# Ai_Breakout_OLED-0_962.net
KiCad netlist of a schematic drawn in EAGLE
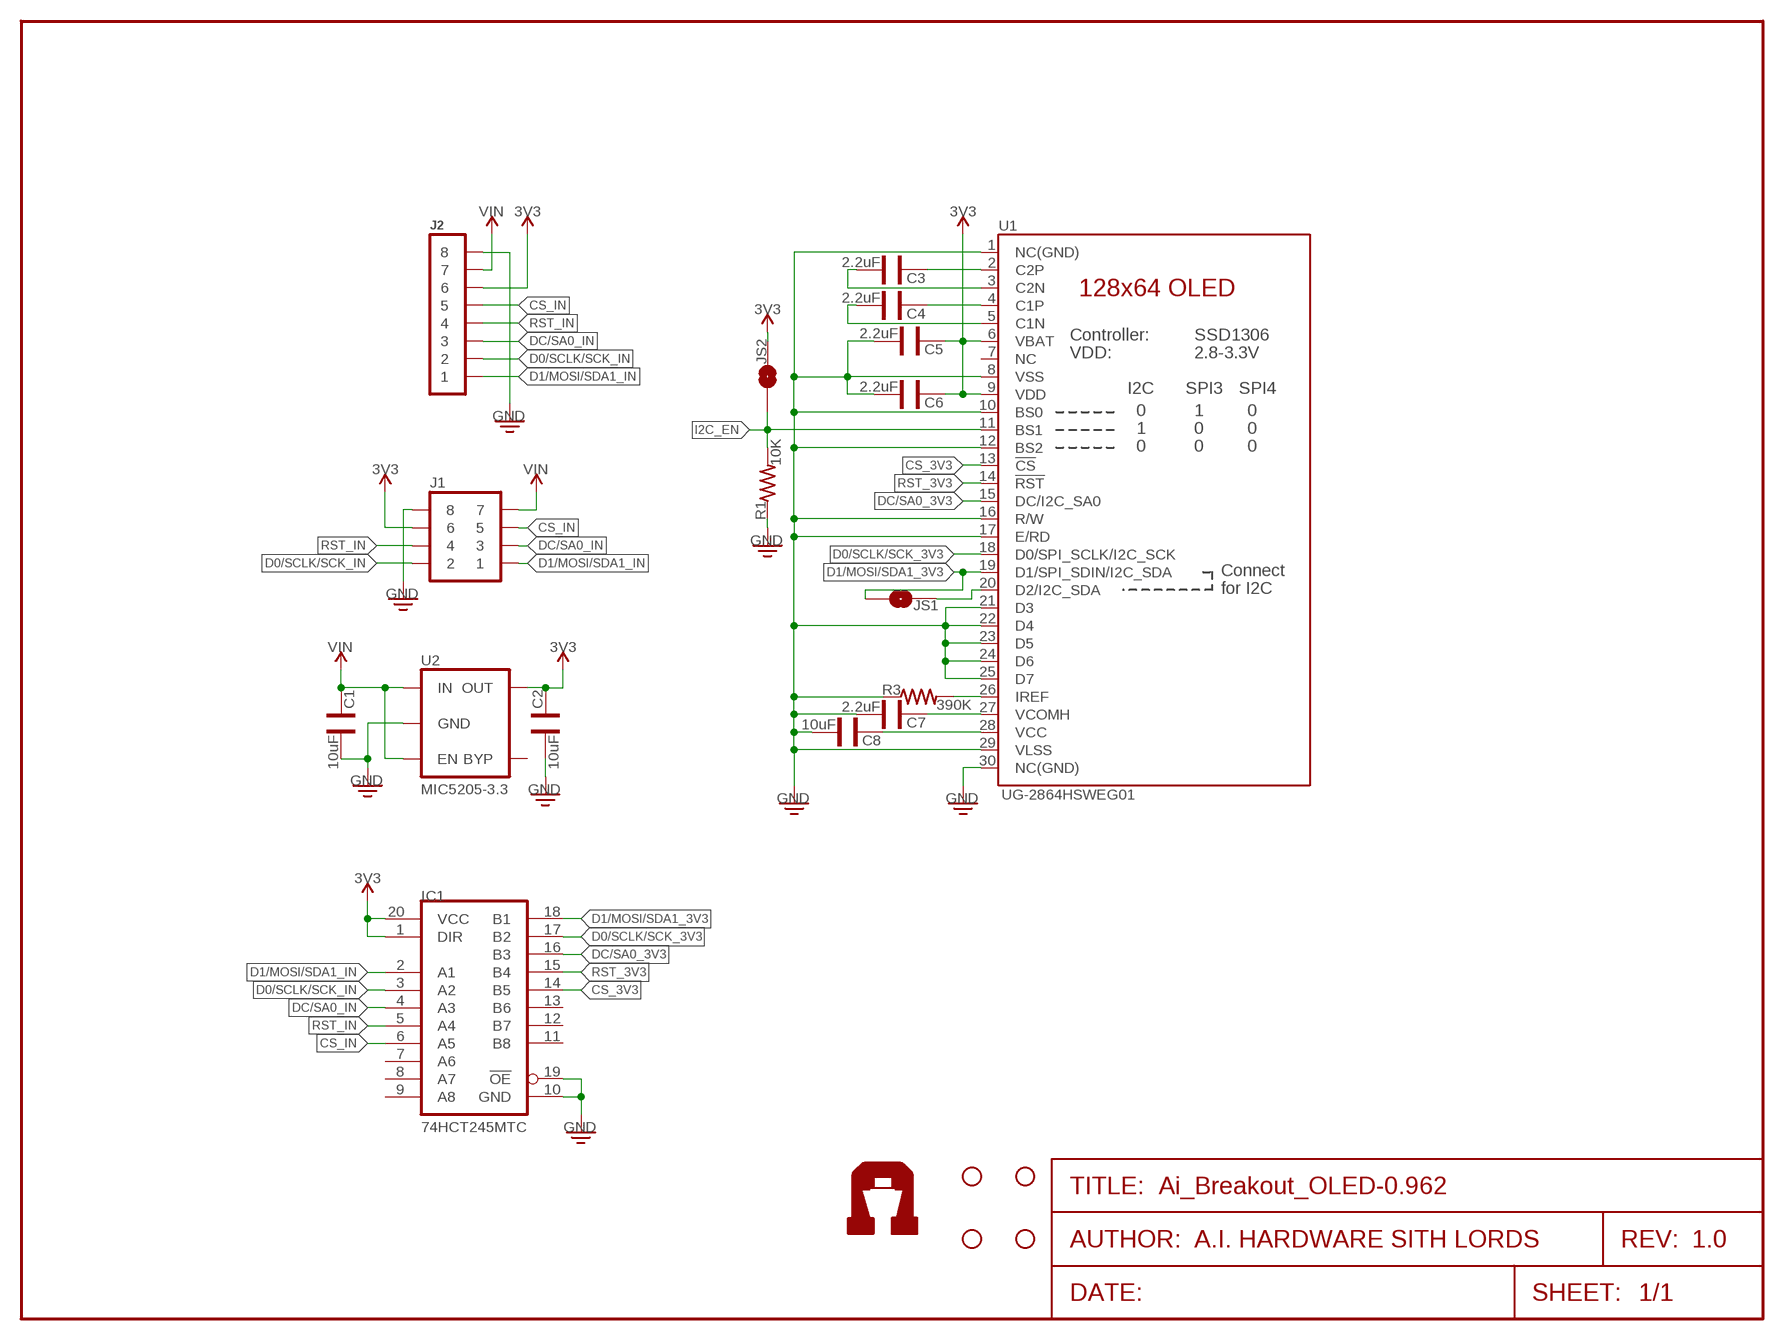
[diagram p0: schematic, sheet 1]

(export (version "E")
  (design (tool "Eeschema 10.0.6"))
  (components
    (comp (ref "C1")
      (value "10uF")
      (footprint "eagle-import:CAP-0603")
      (libsource (lib "eagle-import") (part "CAP0603"))
    )
    (comp (ref "C2")
      (value "10uF")
      (footprint "eagle-import:CAP-0603")
      (libsource (lib "eagle-import") (part "CAP0603"))
    )
    (comp (ref "C3")
      (value "2.2uF")
      (footprint "eagle-import:CAP-0603")
      (libsource (lib "eagle-import") (part "CAP0603"))
    )
    (comp (ref "C4")
      (value "2.2uF")
      (footprint "eagle-import:CAP-0603")
      (libsource (lib "eagle-import") (part "CAP0603"))
    )
    (comp (ref "C5")
      (value "2.2uF")
      (footprint "eagle-import:CAP-0603")
      (libsource (lib "eagle-import") (part "CAP0603"))
    )
    (comp (ref "C6")
      (value "2.2uF")
      (footprint "eagle-import:CAP-0603")
      (libsource (lib "eagle-import") (part "CAP0603"))
    )
    (comp (ref "C7")
      (value "2.2uF")
      (footprint "eagle-import:CAP-0603")
      (libsource (lib "eagle-import") (part "CAP0603"))
    )
    (comp (ref "C8")
      (value "10uF")
      (footprint "eagle-import:CAP-0603")
      (libsource (lib "eagle-import") (part "CAP0603"))
    )
    (comp (ref "IC1")
      (value "74HCT245MTC")
      (footprint "eagle-import:SSOP20")
      (libsource (lib "eagle-import") (part "74HCT245MTC"))
    )
    (comp (ref "J1")
      (value "2X04")
      (footprint "eagle-import:2X04")
      (libsource (lib "eagle-import") (part "2X04"))
    )
    (comp (ref "J2")
      (value "1X08")
      (footprint "eagle-import:1X08")
      (libsource (lib "eagle-import") (part "1X08"))
    )
    (comp (ref "JS1")
      (value "1X02-SJ-NO")
      (footprint "eagle-import:1X02-SJ-NO")
      (libsource (lib "eagle-import") (part "1X02-SJ-NO"))
    )
    (comp (ref "JS2")
      (value "1X02-SJ-NO")
      (footprint "eagle-import:1X02-SJ-NO")
      (libsource (lib "eagle-import") (part "1X02-SJ-NO"))
    )
    (comp (ref "M1")
      (value "STAND-OFF")
      (footprint "eagle-import:STAND-OFF")
      (libsource (lib "eagle-import") (part "STAND-OFF"))
    )
    (comp (ref "M2")
      (value "STAND-OFF")
      (footprint "eagle-import:STAND-OFF")
      (libsource (lib "eagle-import") (part "STAND-OFF"))
    )
    (comp (ref "M3")
      (value "STAND-OFF")
      (footprint "eagle-import:STAND-OFF")
      (libsource (lib "eagle-import") (part "STAND-OFF"))
    )
    (comp (ref "M4")
      (value "STAND-OFF")
      (footprint "eagle-import:STAND-OFF")
      (libsource (lib "eagle-import") (part "STAND-OFF"))
    )
    (comp (ref "R1")
      (value "10K")
      (footprint "eagle-import:RES-0603")
      (libsource (lib "eagle-import") (part "RES0603"))
    )
    (comp (ref "R3")
      (value "390K")
      (footprint "eagle-import:RES-0603")
      (libsource (lib "eagle-import") (part "RES0603"))
    )
    (comp (ref "U$15")
      (value "AI-LOGOXS")
      (footprint "eagle-import:AI-LOGO-XS")
      (libsource (lib "eagle-import") (part "AI-LOGOXS"))
    )
    (comp (ref "U$16")
      (value "AI-LOGOXS")
      (footprint "eagle-import:AI-LOGO-XS")
      (libsource (lib "eagle-import") (part "AI-LOGOXS"))
    )
    (comp (ref "U1")
      (value "UG-2864HSWEG01")
      (footprint "eagle-import:UG-2864HSWEG01_0.96_WRAP")
      (libsource (lib "eagle-import") (part "UG-2864HSWEG01-0.96"))
    )
    (comp (ref "U2")
      (value "MIC5205-3.3")
      (footprint "eagle-import:SOT23-5")
      (libsource (lib "eagle-import") (part "MIC5205-3.3"))
    )
  )
  (nets
    (net (code "1") (name "3V3") (class "Default")
      (node (ref "C2") (pin "2") (pinfunction "2_2") (pintype "passive"))
      (node (ref "C5") (pin "2") (pinfunction "2_2") (pintype "passive"))
      (node (ref "C6") (pin "2") (pinfunction "2_2") (pintype "passive"))
      (node (ref "IC1") (pin "1") (pinfunction "DIR_1") (pintype "input"))
      (node (ref "IC1") (pin "20") (pinfunction "VCC_20") (pintype "power_in"))
      (node (ref "J1") (pin "6") (pinfunction "6_6") (pintype "bidirectional"))
      (node (ref "J2") (pin "6") (pinfunction "6_6") (pintype "bidirectional"))
      (node (ref "JS2") (pin "2") (pinfunction "2_2") (pintype "passive"))
      (node (ref "U1") (pin "6") (pinfunction "VBAT_6") (pintype "input"))
      (node (ref "U1") (pin "9") (pinfunction "VDD_9") (pintype "power_in"))
      (node (ref "U2") (pin "5") (pinfunction "OUT_5") (pintype "passive"))
    )
    (net (code "2") (name "CS_3V3") (class "Default")
      (node (ref "IC1") (pin "14") (pinfunction "B5_14") (pintype "bidirectional"))
      (node (ref "U1") (pin "13") (pinfunction "~{CS}_13") (pintype "input"))
    )
    (net (code "3") (name "CS_IN") (class "Default")
      (node (ref "IC1") (pin "6") (pinfunction "A5_6") (pintype "bidirectional"))
      (node (ref "J1") (pin "5") (pinfunction "5_5") (pintype "bidirectional"))
      (node (ref "J2") (pin "5") (pinfunction "5_5") (pintype "bidirectional"))
    )
    (net (code "4") (name "D0{slash}SCLK{slash}SCK_3V3") (class "Default")
      (node (ref "IC1") (pin "17") (pinfunction "B2_17") (pintype "bidirectional"))
      (node (ref "U1") (pin "18") (pinfunction "D0/SPI_SCLK/I2C_SCK_18") (pintype "bidirectional"))
    )
    (net (code "5") (name "D0{slash}SCLK{slash}SCK_IN") (class "Default")
      (node (ref "IC1") (pin "3") (pinfunction "A2_3") (pintype "bidirectional"))
      (node (ref "J1") (pin "2") (pinfunction "2_2") (pintype "bidirectional"))
      (node (ref "J2") (pin "2") (pinfunction "2_2") (pintype "bidirectional"))
    )
    (net (code "6") (name "D1{slash}MOSI{slash}SDA1_3V3") (class "Default")
      (node (ref "IC1") (pin "18") (pinfunction "B1_18") (pintype "bidirectional"))
      (node (ref "JS1") (pin "1") (pinfunction "1_1") (pintype "passive"))
      (node (ref "U1") (pin "19") (pinfunction "D1/SPI_SDIN/I2C_SDA_19") (pintype "bidirectional"))
    )
    (net (code "7") (name "D1{slash}MOSI{slash}SDA1_IN") (class "Default")
      (node (ref "IC1") (pin "2") (pinfunction "A1_2") (pintype "bidirectional"))
      (node (ref "J1") (pin "1") (pinfunction "1_1") (pintype "bidirectional"))
      (node (ref "J2") (pin "1") (pinfunction "1_1") (pintype "bidirectional"))
    )
    (net (code "8") (name "DC{slash}SA0_3V3") (class "Default")
      (node (ref "IC1") (pin "16") (pinfunction "B3_16") (pintype "bidirectional"))
      (node (ref "U1") (pin "15") (pinfunction "DC/I2C_SA0_15") (pintype "input"))
    )
    (net (code "9") (name "DC{slash}SA0_IN") (class "Default")
      (node (ref "IC1") (pin "4") (pinfunction "A3_4") (pintype "bidirectional"))
      (node (ref "J1") (pin "3") (pinfunction "3_3") (pintype "bidirectional"))
      (node (ref "J2") (pin "3") (pinfunction "3_3") (pintype "bidirectional"))
    )
    (net (code "10") (name "GND") (class "Default")
      (node (ref "C1") (pin "1") (pinfunction "1_1") (pintype "passive"))
      (node (ref "C2") (pin "1") (pinfunction "1_1") (pintype "passive"))
      (node (ref "C5") (pin "1") (pinfunction "1_1") (pintype "passive"))
      (node (ref "C6") (pin "1") (pinfunction "1_1") (pintype "passive"))
      (node (ref "C7") (pin "1") (pinfunction "1_1") (pintype "passive"))
      (node (ref "C8") (pin "1") (pinfunction "1_1") (pintype "passive"))
      (node (ref "IC1") (pin "10") (pinfunction "GND_10") (pintype "power_in"))
      (node (ref "IC1") (pin "19") (pinfunction "~{OE}_19") (pintype "input"))
      (node (ref "J1") (pin "8") (pinfunction "8_8") (pintype "bidirectional"))
      (node (ref "J2") (pin "8") (pinfunction "8_8") (pintype "bidirectional"))
      (node (ref "R1") (pin "1") (pinfunction "1_1") (pintype "passive"))
      (node (ref "R3") (pin "1") (pinfunction "1_1") (pintype "passive"))
      (node (ref "U1") (pin "1") (pinfunction "NC(GND)_1") (pintype "input"))
      (node (ref "U1") (pin "10") (pinfunction "BS0_10") (pintype "input"))
      (node (ref "U1") (pin "12") (pinfunction "BS2_12") (pintype "input"))
      (node (ref "U1") (pin "16") (pinfunction "R/W_16") (pintype "input"))
      (node (ref "U1") (pin "17") (pinfunction "E/RD_17") (pintype "input"))
      (node (ref "U1") (pin "21") (pinfunction "D3_21") (pintype "bidirectional"))
      (node (ref "U1") (pin "22") (pinfunction "D4_22") (pintype "bidirectional"))
      (node (ref "U1") (pin "23") (pinfunction "D5_23") (pintype "bidirectional"))
      (node (ref "U1") (pin "24") (pinfunction "D6_24") (pintype "bidirectional"))
      (node (ref "U1") (pin "25") (pinfunction "D7_25") (pintype "bidirectional"))
      (node (ref "U1") (pin "29") (pinfunction "VLSS_29") (pintype "power_in"))
      (node (ref "U1") (pin "30") (pinfunction "NC(GND)_30") (pintype "input"))
      (node (ref "U1") (pin "8") (pinfunction "VSS_8") (pintype "power_in"))
      (node (ref "U2") (pin "2") (pinfunction "GND_2") (pintype "input"))
    )
    (net (code "11") (name "I2C_EN") (class "Default")
      (node (ref "JS2") (pin "1") (pinfunction "1_1") (pintype "passive"))
      (node (ref "R1") (pin "2") (pinfunction "2_2") (pintype "passive"))
      (node (ref "U1") (pin "11") (pinfunction "BS1_11") (pintype "input"))
    )
    (net (code "12") (name "Net-(U1-C1N)") (class "Default")
      (node (ref "C4") (pin "1") (pinfunction "1_1") (pintype "passive"))
      (node (ref "U1") (pin "5") (pinfunction "C1N_5") (pintype "input"))
    )
    (net (code "13") (name "Net-(U1-C1P)") (class "Default")
      (node (ref "C4") (pin "2") (pinfunction "2_2") (pintype "passive"))
      (node (ref "U1") (pin "4") (pinfunction "C1P_4") (pintype "input"))
    )
    (net (code "14") (name "Net-(U1-C2N)") (class "Default")
      (node (ref "C3") (pin "1") (pinfunction "1_1") (pintype "passive"))
      (node (ref "U1") (pin "3") (pinfunction "C2N_3") (pintype "input"))
    )
    (net (code "15") (name "Net-(U1-C2P)") (class "Default")
      (node (ref "C3") (pin "2") (pinfunction "2_2") (pintype "passive"))
      (node (ref "U1") (pin "2") (pinfunction "C2P_2") (pintype "input"))
    )
    (net (code "16") (name "Net-(U1-D2{slash}I2C_SDA)") (class "Default")
      (node (ref "JS1") (pin "2") (pinfunction "2_2") (pintype "passive"))
      (node (ref "U1") (pin "20") (pinfunction "D2/I2C_SDA_20") (pintype "bidirectional"))
    )
    (net (code "17") (name "Net-(U1-IREF)") (class "Default")
      (node (ref "R3") (pin "2") (pinfunction "2_2") (pintype "passive"))
      (node (ref "U1") (pin "26") (pinfunction "IREF_26") (pintype "input"))
    )
    (net (code "18") (name "Net-(U1-VCC)") (class "Default")
      (node (ref "C8") (pin "2") (pinfunction "2_2") (pintype "passive"))
      (node (ref "U1") (pin "28") (pinfunction "VCC_28") (pintype "power_in"))
    )
    (net (code "19") (name "Net-(U1-VCOMH)") (class "Default")
      (node (ref "C7") (pin "2") (pinfunction "2_2") (pintype "passive"))
      (node (ref "U1") (pin "27") (pinfunction "VCOMH_27") (pintype "output"))
    )
    (net (code "20") (name "RST_3V3") (class "Default")
      (node (ref "IC1") (pin "15") (pinfunction "B4_15") (pintype "bidirectional"))
      (node (ref "U1") (pin "14") (pinfunction "~{RST}_14") (pintype "input"))
    )
    (net (code "21") (name "RST_IN") (class "Default")
      (node (ref "IC1") (pin "5") (pinfunction "A4_5") (pintype "bidirectional"))
      (node (ref "J1") (pin "4") (pinfunction "4_4") (pintype "bidirectional"))
      (node (ref "J2") (pin "4") (pinfunction "4_4") (pintype "bidirectional"))
    )
    (net (code "22") (name "VIN") (class "Default")
      (node (ref "C1") (pin "2") (pinfunction "2_2") (pintype "passive"))
      (node (ref "J1") (pin "7") (pinfunction "7_7") (pintype "bidirectional"))
      (node (ref "J2") (pin "7") (pinfunction "7_7") (pintype "bidirectional"))
      (node (ref "U2") (pin "1") (pinfunction "IN_1") (pintype "input"))
      (node (ref "U2") (pin "3") (pinfunction "EN_3") (pintype "input"))
    )
    (net (code "23") (name "unconnected-(IC1-A6-Pad7)") (class "Default")
      (node (ref "IC1") (pin "7") (pinfunction "A6_7") (pintype "bidirectional"))
    )
    (net (code "24") (name "unconnected-(IC1-A7-Pad8)") (class "Default")
      (node (ref "IC1") (pin "8") (pinfunction "A7_8") (pintype "bidirectional"))
    )
    (net (code "25") (name "unconnected-(IC1-A8-Pad9)") (class "Default")
      (node (ref "IC1") (pin "9") (pinfunction "A8_9") (pintype "bidirectional"))
    )
    (net (code "26") (name "unconnected-(IC1-B6-Pad13)") (class "Default")
      (node (ref "IC1") (pin "13") (pinfunction "B6_13") (pintype "bidirectional"))
    )
    (net (code "27") (name "unconnected-(IC1-B7-Pad12)") (class "Default")
      (node (ref "IC1") (pin "12") (pinfunction "B7_12") (pintype "bidirectional"))
    )
    (net (code "28") (name "unconnected-(IC1-B8-Pad11)") (class "Default")
      (node (ref "IC1") (pin "11") (pinfunction "B8_11") (pintype "bidirectional"))
    )
    (net (code "29") (name "unconnected-(U1-NC-Pad7)") (class "Default")
      (node (ref "U1") (pin "7") (pinfunction "NC_7") (pintype "no_connect"))
    )
    (net (code "30") (name "unconnected-(U2-BYP-Pad4)") (class "Default")
      (node (ref "U2") (pin "4") (pinfunction "BYP_4") (pintype "input"))
    )
  )
)
